# Stepper_Driver_Sheet3.net
KiCad netlist of a schematic drawn in Altium Designer
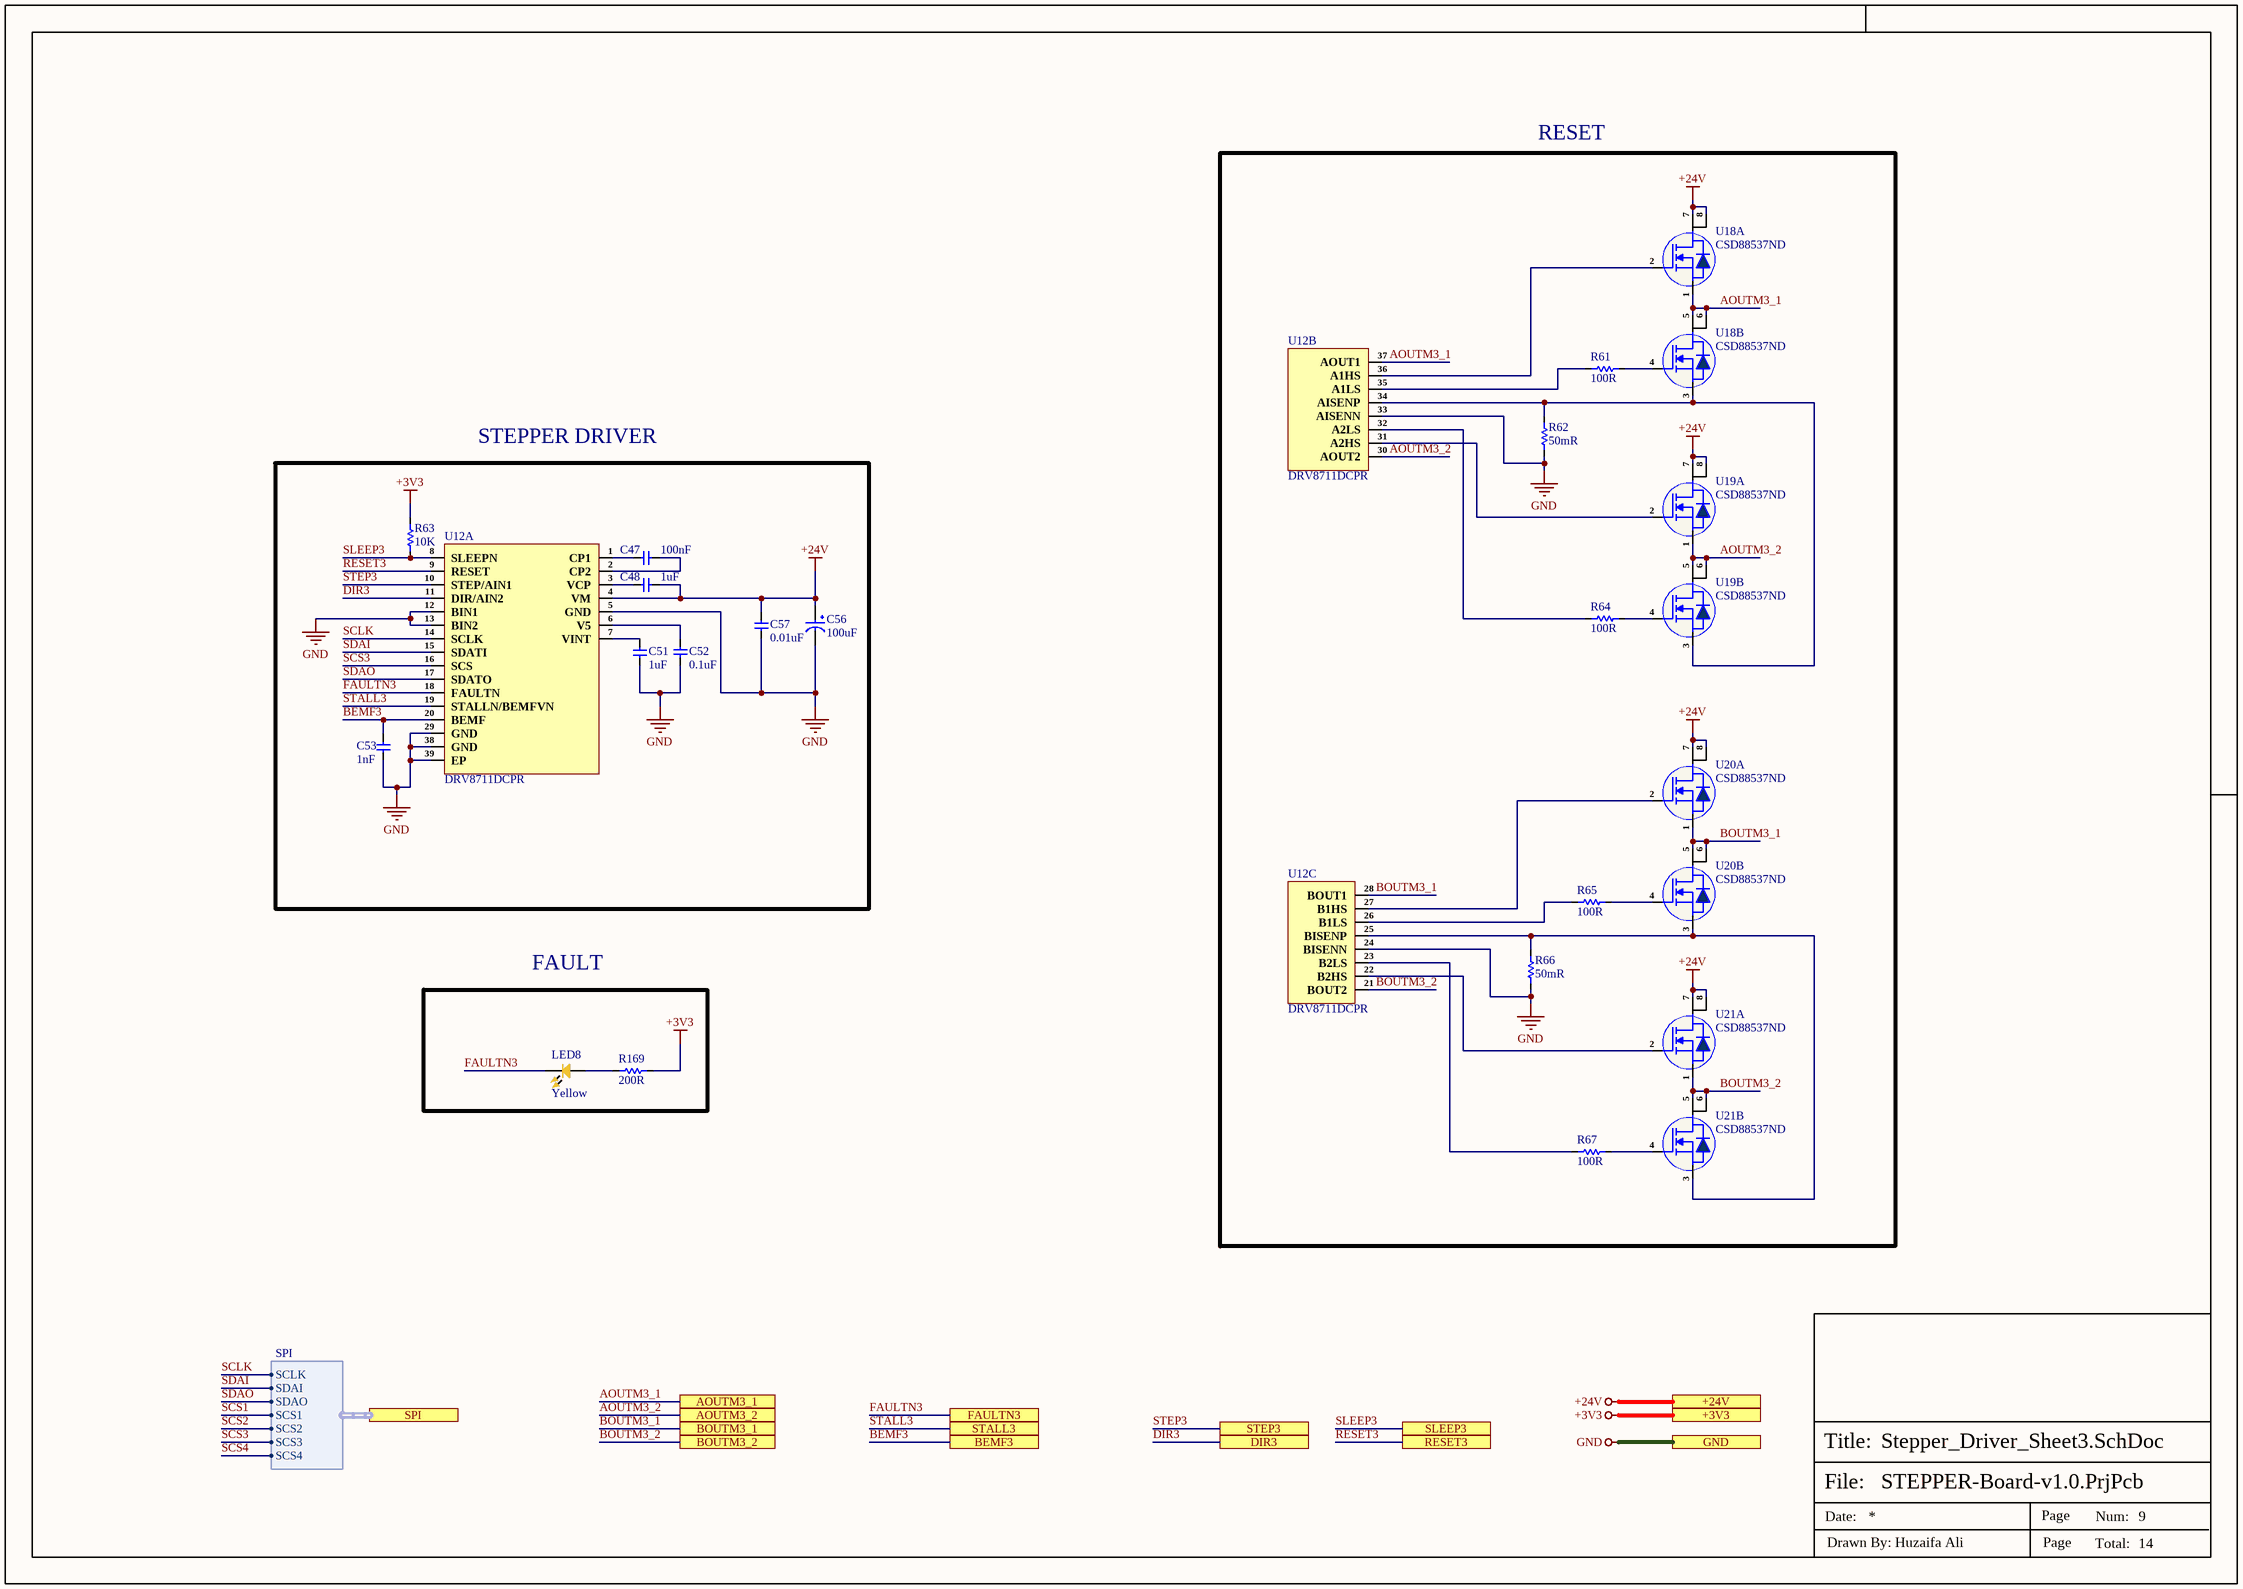
[diagram p0: Stepper_Driver_Sheet3.SchDoc]

(export (version "E")
  (design (tool "Eeschema 10.0.6"))
  (components
    (comp (ref "C47")
      (value "100nF")
      (footprint "cap-0402")
      (description "CAP CER 0.1UF 50V X7R 0402")
      (fields
        (field (name "MANUFACTURER") "TDK")
        (field (name "MANUFACTURER PART NUMBER") "C1005X7R1H104KT000F")
      )
      (libsource (lib "eSpark Libraries") (part "C1005X7R1H104KT000F"))
    )
    (comp (ref "C48")
      (value "1uF")
      (footprint "Cap-0402")
      (description "CAP CER 1UF 10V X5R 0402")
      (fields
        (field (name "MANUFACTURER") "Yageo")
        (field (name "MANUFACTURER PART NUMBER") "CC0402KRX5R6BB105")
      )
      (libsource (lib "eSpark Libraries") (part "CC0402KRX5R6BB105"))
    )
    (comp (ref "C51")
      (value "1uF")
      (footprint "Cap-0402")
      (description "CAP CER 1UF 10V X5R 0402")
      (fields
        (field (name "MANUFACTURER") "Yageo")
        (field (name "MANUFACTURER PART NUMBER") "CC0402KRX5R6BB105")
      )
      (libsource (lib "eSpark Libraries") (part "CC0402KRX5R6BB105"))
    )
    (comp (ref "C52")
      (value "0.1uF")
      (footprint "Cap-0402")
      (description "CAP CER 0.1UF 16V X7R 0402")
      (fields
        (field (name "MANUFACTURER") "Yageo")
        (field (name "MANUFACTURER PART NUMBER") "CC0402JRX7R7BB104")
      )
      (libsource (lib "eSpark Libraries") (part "CC0402JRX7R7BB104"))
    )
    (comp (ref "C53")
      (value "1nF")
      (footprint "Cap-0402")
      (description "CAP CER 1000PF 25V C0G 0402")
      (fields
        (field (name "MANUFACTURER") "TDK")
        (field (name "MANUFACTURER PART NUMBER") "C1005C0G1E102JT000F")
      )
      (libsource (lib "eSpark Libraries") (part "C1005C0G1E102JT000F"))
    )
    (comp (ref "C56")
      (value "100uF")
      (footprint "UWT1H101MNL1GS_")
      (description "CAP ALUM 100UF 20% 50V SMD")
      (fields
        (field (name "MANUFACTURER") "Nichicon")
        (field (name "MANUFACTURER PART NUMBER") "UWT1H101MNL1GS")
      )
      (libsource (lib "eSpark Libraries") (part "UWT1H101MNL1GS"))
    )
    (comp (ref "C57")
      (value "0.01uF")
      (footprint "Cap-0603")
      (description "CAP CER 10000PF 50V C0G/NP0 0603")
      (fields
        (field (name "MANUFACTURER") "Murata")
        (field (name "MANUFACTURER PART NUMBER") "GRM1885C1H103JA01D")
      )
      (libsource (lib "eSpark Libraries") (part "GRM1885C1H103JA01D"))
    )
    (comp (ref "LED8")
      (value "Yellow")
      (footprint "LED-0603")
      (description "yellow 0603 Light Emitting Diodes (LED) ROHS")
      (fields
        (field (name "MANUFACTURER") "Foshan NationStar Optoelectronics")
        (field (name "MANUFACTURER PART NUMBER") "NCD0603Y2")
      )
      (libsource (lib "eSpark Libraries") (part "NCD0603Y2"))
    )
    (comp (ref "R61")
      (value "100R")
      (footprint "Res-0402")
      (description "RES 100 OHM 1% 1/16W 0402")
      (fields
        (field (name "MANUFACTURER") "Yageo")
        (field (name "MANUFACTURER PART NUMBER") "RC0402FR-07100RL")
      )
      (libsource (lib "eSpark Libraries") (part "RC0402FR-07100RL"))
    )
    (comp (ref "R62")
      (value "50mR")
      (footprint "RES-2010")
      (fields
        (field (name "MANUFACTURER") "TA-I Tech")
        (field (name "MANUFACTURER PART NUMBER") "RLM20FECR050")
        (field (name "LCSC PART NUMBER") "C912938")
      )
      (libsource (lib "eSpark Libraries") (part "RLM20FECR050"))
    )
    (comp (ref "R63")
      (value "10K")
      (footprint "Res-0402")
      (description "RES 10K OHM 1% 1/16W 0402")
      (fields
        (field (name "MANUFACTURER") "Yageo")
        (field (name "MANUFACTURER PART NUMBER") "RC0402FR-0710KL")
      )
      (libsource (lib "eSpark Libraries") (part "RC0402FR-0710KL"))
    )
    (comp (ref "R64")
      (value "100R")
      (footprint "Res-0402")
      (description "RES 100 OHM 1% 1/16W 0402")
      (fields
        (field (name "MANUFACTURER") "Yageo")
        (field (name "MANUFACTURER PART NUMBER") "RC0402FR-07100RL")
      )
      (libsource (lib "eSpark Libraries") (part "RC0402FR-07100RL"))
    )
    (comp (ref "R65")
      (value "100R")
      (footprint "Res-0402")
      (description "RES 100 OHM 1% 1/16W 0402")
      (fields
        (field (name "MANUFACTURER") "Yageo")
        (field (name "MANUFACTURER PART NUMBER") "RC0402FR-07100RL")
      )
      (libsource (lib "eSpark Libraries") (part "RC0402FR-07100RL"))
    )
    (comp (ref "R66")
      (value "50mR")
      (footprint "RES-2010")
      (fields
        (field (name "MANUFACTURER") "TA-I Tech")
        (field (name "MANUFACTURER PART NUMBER") "RLM20FECR050")
        (field (name "LCSC PART NUMBER") "C912938")
      )
      (libsource (lib "eSpark Libraries") (part "RLM20FECR050"))
    )
    (comp (ref "R67")
      (value "100R")
      (footprint "Res-0402")
      (description "RES 100 OHM 1% 1/16W 0402")
      (fields
        (field (name "MANUFACTURER") "Yageo")
        (field (name "MANUFACTURER PART NUMBER") "RC0402FR-07100RL")
      )
      (libsource (lib "eSpark Libraries") (part "RC0402FR-07100RL"))
    )
    (comp (ref "R169")
      (value "200R")
      (footprint "Res-0402")
      (description "RES 200 OHM 1% 1/16W 0402")
      (fields
        (field (name "MANUFACTURER") "Yageo")
        (field (name "MANUFACTURER PART NUMBER") "RC0402FR-07200RL")
      )
      (libsource (lib "eSpark Libraries") (part "RC0402FR-07200RL"))
    )
    (comp (ref "U12")
      (value "DRV8711DCPR")
      (footprint "HTSSOP-38-EP-4.4mm")
      (description "IC MTR DRV BIPOLR 8-52V 38HTSSOP")
      (fields (field (name "LCSC PART NUMBER") "C60013") (field (name "MANUFACTURER") "Texas Instruments"))
      (libsource (lib "eSpark Libraries") (part "DRV8711DCPR"))
    )
    (comp (ref "U18")
      (value "CSD88537ND")
      (footprint "SOIC-8")
      (description "MOSFET 2N-CH 60V 15A 8SOIC")
      (fields (field (name "LCSC PART NUMBER") "C117439") (field (name "MANUFACTURER") "Texas Instruments"))
      (libsource (lib "eSpark Libraries") (part "CSD88537ND"))
    )
    (comp (ref "U19")
      (value "CSD88537ND")
      (footprint "SOIC-8")
      (description "MOSFET 2N-CH 60V 15A 8SOIC")
      (fields (field (name "LCSC PART NUMBER") "C117439") (field (name "MANUFACTURER") "Texas Instruments"))
      (libsource (lib "eSpark Libraries") (part "CSD88537ND"))
    )
    (comp (ref "U20")
      (value "CSD88537ND")
      (footprint "SOIC-8")
      (description "MOSFET 2N-CH 60V 15A 8SOIC")
      (fields (field (name "LCSC PART NUMBER") "C117439") (field (name "MANUFACTURER") "Texas Instruments"))
      (libsource (lib "eSpark Libraries") (part "CSD88537ND"))
    )
    (comp (ref "U21")
      (value "CSD88537ND")
      (footprint "SOIC-8")
      (description "MOSFET 2N-CH 60V 15A 8SOIC")
      (fields (field (name "LCSC PART NUMBER") "C117439") (field (name "MANUFACTURER") "Texas Instruments"))
      (libsource (lib "eSpark Libraries") (part "CSD88537ND"))
    )
  )
  (nets
    (net (code "2") (name "+3V3") (class "Default")
      (node (ref "R169") (pin "2") (pinfunction "2_2") (pintype "passive"))
      (node (ref "R63") (pin "1") (pinfunction "1_1") (pintype "passive"))
    )
    (net (code "3") (name "+24V") (class "Default")
      (node (ref "C48") (pin "2") (pinfunction "2_2") (pintype "passive"))
      (node (ref "C56") (pin "1") (pinfunction "1_1") (pintype "passive"))
      (node (ref "C57") (pin "2") (pinfunction "2_2") (pintype "passive"))
      (node (ref "U12") (pin "4") (pinfunction "VM_4") (pintype "passive"))
      (node (ref "U18") (pin "7") (pinfunction "D1_7") (pintype "passive"))
      (node (ref "U18") (pin "8") (pinfunction "D1_8") (pintype "passive"))
      (node (ref "U19") (pin "7") (pinfunction "D1_7") (pintype "passive"))
      (node (ref "U19") (pin "8") (pinfunction "D1_8") (pintype "passive"))
      (node (ref "U20") (pin "7") (pinfunction "D1_7") (pintype "passive"))
      (node (ref "U20") (pin "8") (pinfunction "D1_8") (pintype "passive"))
      (node (ref "U21") (pin "7") (pinfunction "D1_7") (pintype "passive"))
      (node (ref "U21") (pin "8") (pinfunction "D1_8") (pintype "passive"))
    )
    (net (code "4") (name "/AOUTM3_1") (class "Default")
      (node (ref "U12") (pin "37") (pinfunction "AOUT1_37") (pintype "passive"))
      (node (ref "U18") (pin "1") (pinfunction "S1_1") (pintype "passive"))
      (node (ref "U18") (pin "5") (pinfunction "D2_5") (pintype "passive"))
      (node (ref "U18") (pin "6") (pinfunction "D2_6") (pintype "passive"))
    )
    (net (code "5") (name "/AOUTM3_2") (class "Default")
      (node (ref "U12") (pin "30") (pinfunction "AOUT2_30") (pintype "passive"))
      (node (ref "U19") (pin "1") (pinfunction "S1_1") (pintype "passive"))
      (node (ref "U19") (pin "5") (pinfunction "D2_5") (pintype "passive"))
      (node (ref "U19") (pin "6") (pinfunction "D2_6") (pintype "passive"))
    )
    (net (code "6") (name "/BEMF3") (class "Default")
      (node (ref "C53") (pin "2") (pinfunction "2_2") (pintype "passive"))
      (node (ref "U12") (pin "20") (pinfunction "BEMF_20") (pintype "passive"))
    )
    (net (code "7") (name "/BOUTM3_1") (class "Default")
      (node (ref "U12") (pin "28") (pinfunction "BOUT1_28") (pintype "passive"))
      (node (ref "U20") (pin "1") (pinfunction "S1_1") (pintype "passive"))
      (node (ref "U20") (pin "5") (pinfunction "D2_5") (pintype "passive"))
      (node (ref "U20") (pin "6") (pinfunction "D2_6") (pintype "passive"))
    )
    (net (code "8") (name "/BOUTM3_2") (class "Default")
      (node (ref "U12") (pin "21") (pinfunction "BOUT2_21") (pintype "passive"))
      (node (ref "U21") (pin "1") (pinfunction "S1_1") (pintype "passive"))
      (node (ref "U21") (pin "5") (pinfunction "D2_5") (pintype "passive"))
      (node (ref "U21") (pin "6") (pinfunction "D2_6") (pintype "passive"))
    )
    (net (code "9") (name "/DIR3") (class "Default")
      (node (ref "U12") (pin "11") (pinfunction "DIR/AIN2_11") (pintype "passive"))
    )
    (net (code "10") (name "/FAULTN3") (class "Default")
      (node (ref "LED8") (pin "2") (pinfunction "2_2") (pintype "passive"))
      (node (ref "U12") (pin "18") (pinfunction "FAULTN_18") (pintype "passive"))
    )
    (net (code "11") (name "/RESET3") (class "Default")
      (node (ref "U12") (pin "9") (pinfunction "RESET_9") (pintype "passive"))
    )
    (net (code "12") (name "/SCLK") (class "Default")
      (node (ref "U12") (pin "14") (pinfunction "SCLK_14") (pintype "passive"))
    )
    (net (code "15") (name "/SCS3") (class "Default")
      (node (ref "U12") (pin "16") (pinfunction "SCS_16") (pintype "passive"))
    )
    (net (code "17") (name "/SDAI") (class "Default")
      (node (ref "U12") (pin "15") (pinfunction "SDATI_15") (pintype "passive"))
    )
    (net (code "18") (name "/SDAO") (class "Default")
      (node (ref "U12") (pin "17") (pinfunction "SDATO_17") (pintype "passive"))
    )
    (net (code "19") (name "/SLEEP3") (class "Default")
      (node (ref "R63") (pin "2") (pinfunction "2_2") (pintype "passive"))
      (node (ref "U12") (pin "8") (pinfunction "SLEEPN_8") (pintype "passive"))
    )
    (net (code "20") (name "/STALL3") (class "Default")
      (node (ref "U12") (pin "19") (pinfunction "STALLN/BEMFVN_19") (pintype "passive"))
    )
    (net (code "21") (name "/STEP3") (class "Default")
      (node (ref "U12") (pin "10") (pinfunction "STEP/AIN1_10") (pintype "passive"))
    )
    (net (code "23") (name "GND") (class "Default")
      (node (ref "C51") (pin "1") (pinfunction "1_1") (pintype "passive"))
      (node (ref "C52") (pin "2") (pinfunction "2_2") (pintype "passive"))
      (node (ref "C53") (pin "1") (pinfunction "1_1") (pintype "passive"))
      (node (ref "C56") (pin "2") (pinfunction "2_2") (pintype "passive"))
      (node (ref "C57") (pin "1") (pinfunction "1_1") (pintype "passive"))
      (node (ref "R62") (pin "1") (pinfunction "1_1") (pintype "passive"))
      (node (ref "R66") (pin "1") (pinfunction "1_1") (pintype "passive"))
      (node (ref "U12") (pin "12") (pinfunction "BIN1_12") (pintype "passive"))
      (node (ref "U12") (pin "13") (pinfunction "BIN2_13") (pintype "passive"))
      (node (ref "U12") (pin "24") (pinfunction "BISENN_24") (pintype "passive"))
      (node (ref "U12") (pin "29") (pinfunction "GND_29") (pintype "passive"))
      (node (ref "U12") (pin "33") (pinfunction "AISENN_33") (pintype "passive"))
      (node (ref "U12") (pin "38") (pinfunction "GND_38") (pintype "passive"))
      (node (ref "U12") (pin "39") (pinfunction "EP_39") (pintype "passive"))
      (node (ref "U12") (pin "5") (pinfunction "GND_5") (pintype "passive"))
    )
    (net (code "24") (name "Net-(LED8-Pad1)") (class "Default")
      (node (ref "LED8") (pin "1") (pinfunction "1_1") (pintype "passive"))
      (node (ref "R169") (pin "1") (pinfunction "1_1") (pintype "passive"))
    )
    (net (code "25") (name "Net-(U12A-CP1)") (class "Default")
      (node (ref "C47") (pin "1") (pinfunction "1_1") (pintype "passive"))
      (node (ref "U12") (pin "1") (pinfunction "CP1_1") (pintype "passive"))
    )
    (net (code "26") (name "Net-(U12A-CP2)") (class "Default")
      (node (ref "C47") (pin "2") (pinfunction "2_2") (pintype "passive"))
      (node (ref "U12") (pin "2") (pinfunction "CP2_2") (pintype "passive"))
    )
    (net (code "27") (name "Net-(U12A-V5)") (class "Default")
      (node (ref "C52") (pin "1") (pinfunction "1_1") (pintype "passive"))
      (node (ref "U12") (pin "6") (pinfunction "V5_6") (pintype "passive"))
    )
    (net (code "28") (name "Net-(U12A-VCP)") (class "Default")
      (node (ref "C48") (pin "1") (pinfunction "1_1") (pintype "passive"))
      (node (ref "U12") (pin "3") (pinfunction "VCP_3") (pintype "passive"))
    )
    (net (code "29") (name "Net-(U12A-VINT)") (class "Default")
      (node (ref "C51") (pin "2") (pinfunction "2_2") (pintype "passive"))
      (node (ref "U12") (pin "7") (pinfunction "VINT_7") (pintype "passive"))
    )
    (net (code "30") (name "Net-(U12B-A1HS)") (class "Default")
      (node (ref "U12") (pin "36") (pinfunction "A1HS_36") (pintype "passive"))
      (node (ref "U18") (pin "2") (pinfunction "G1_2") (pintype "passive"))
    )
    (net (code "31") (name "Net-(U12B-A1LS)") (class "Default")
      (node (ref "R61") (pin "1") (pinfunction "1_1") (pintype "passive"))
      (node (ref "U12") (pin "35") (pinfunction "A1LS_35") (pintype "passive"))
    )
    (net (code "32") (name "Net-(U12B-A2HS)") (class "Default")
      (node (ref "U12") (pin "31") (pinfunction "A2HS_31") (pintype "passive"))
      (node (ref "U19") (pin "2") (pinfunction "G1_2") (pintype "passive"))
    )
    (net (code "33") (name "Net-(U12B-A2LS)") (class "Default")
      (node (ref "R64") (pin "1") (pinfunction "1_1") (pintype "passive"))
      (node (ref "U12") (pin "32") (pinfunction "A2LS_32") (pintype "passive"))
    )
    (net (code "34") (name "Net-(U12B-AISENP)") (class "Default")
      (node (ref "R62") (pin "2") (pinfunction "2_2") (pintype "passive"))
      (node (ref "U12") (pin "34") (pinfunction "AISENP_34") (pintype "passive"))
      (node (ref "U18") (pin "3") (pinfunction "S2_3") (pintype "passive"))
      (node (ref "U19") (pin "3") (pinfunction "S2_3") (pintype "passive"))
    )
    (net (code "35") (name "Net-(U12C-B1HS)") (class "Default")
      (node (ref "U12") (pin "27") (pinfunction "B1HS_27") (pintype "passive"))
      (node (ref "U20") (pin "2") (pinfunction "G1_2") (pintype "passive"))
    )
    (net (code "36") (name "Net-(U12C-B1LS)") (class "Default")
      (node (ref "R65") (pin "1") (pinfunction "1_1") (pintype "passive"))
      (node (ref "U12") (pin "26") (pinfunction "B1LS_26") (pintype "passive"))
    )
    (net (code "37") (name "Net-(U12C-B2HS)") (class "Default")
      (node (ref "U12") (pin "22") (pinfunction "B2HS_22") (pintype "passive"))
      (node (ref "U21") (pin "2") (pinfunction "G1_2") (pintype "passive"))
    )
    (net (code "38") (name "Net-(U12C-B2LS)") (class "Default")
      (node (ref "R67") (pin "1") (pinfunction "1_1") (pintype "passive"))
      (node (ref "U12") (pin "23") (pinfunction "B2LS_23") (pintype "passive"))
    )
    (net (code "39") (name "Net-(U12C-BISENP)") (class "Default")
      (node (ref "R66") (pin "2") (pinfunction "2_2") (pintype "passive"))
      (node (ref "U12") (pin "25") (pinfunction "BISENP_25") (pintype "passive"))
      (node (ref "U20") (pin "3") (pinfunction "S2_3") (pintype "passive"))
      (node (ref "U21") (pin "3") (pinfunction "S2_3") (pintype "passive"))
    )
    (net (code "40") (name "Net-(U18B-G4)") (class "Default")
      (node (ref "R61") (pin "2") (pinfunction "2_2") (pintype "passive"))
      (node (ref "U18") (pin "4") (pinfunction "G4_4") (pintype "passive"))
    )
    (net (code "41") (name "Net-(U19B-G4)") (class "Default")
      (node (ref "R64") (pin "2") (pinfunction "2_2") (pintype "passive"))
      (node (ref "U19") (pin "4") (pinfunction "G4_4") (pintype "passive"))
    )
    (net (code "42") (name "Net-(U20B-G4)") (class "Default")
      (node (ref "R65") (pin "2") (pinfunction "2_2") (pintype "passive"))
      (node (ref "U20") (pin "4") (pinfunction "G4_4") (pintype "passive"))
    )
    (net (code "43") (name "Net-(U21B-G4)") (class "Default")
      (node (ref "R67") (pin "2") (pinfunction "2_2") (pintype "passive"))
      (node (ref "U21") (pin "4") (pinfunction "G4_4") (pintype "passive"))
    )
  )
)
